# Sheet1.net
KiCad netlist of a schematic drawn in Altium Designer
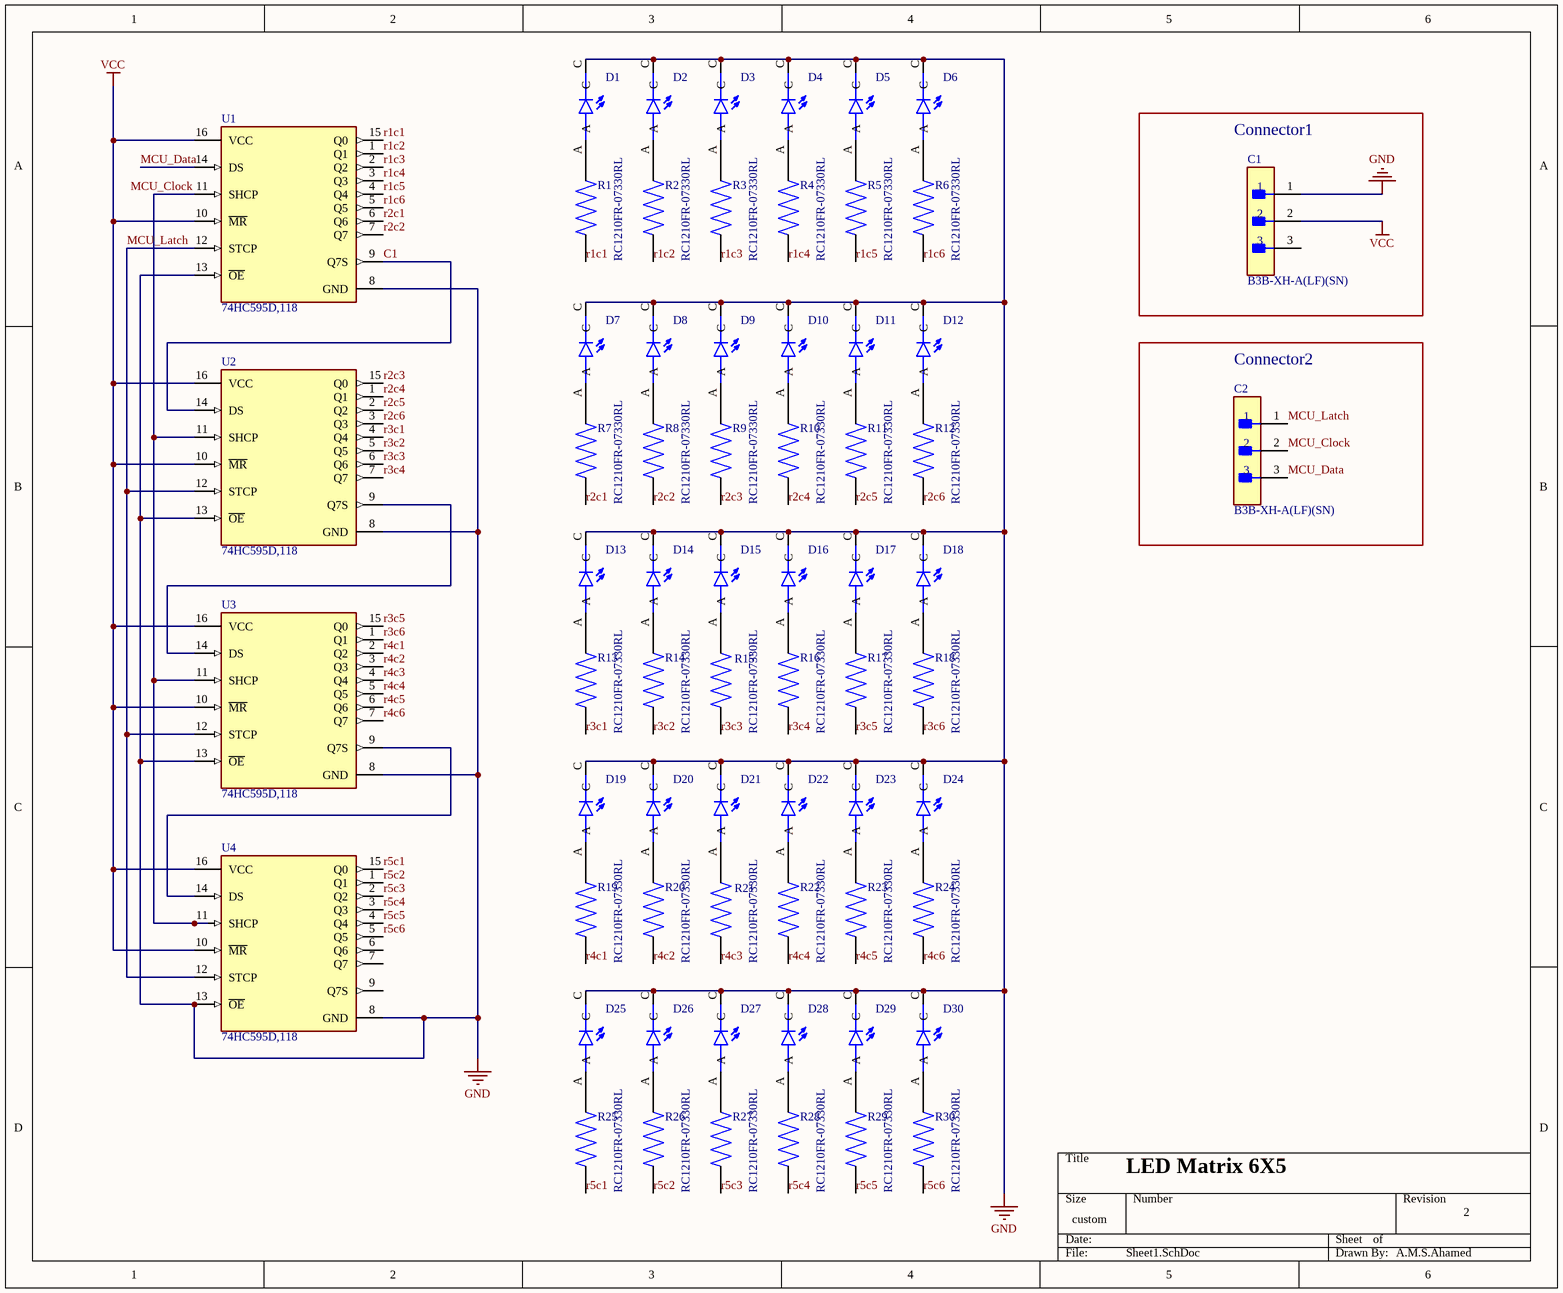
[diagram p0: Sheet1.SchDoc]

(export (version "E")
  (design (tool "Eeschema 10.0.6"))
  (components
    (comp (ref "C1")
      (value "B3B-XH-A(LF)(SN)")
      (footprint "FP-B3B-XH-A_LF_SN-MFG")
      (description "CONN HEADER VERT 3POS 2.5MM")
      (libsource (lib "Altium Content Vault") (part "0d3f023dd272f625e17a2be33dea85f"))
    )
    (comp (ref "C2")
      (value "B3B-XH-A(LF)(SN)")
      (footprint "FP-B3B-XH-A_LF_SN-MFG")
      (description "CONN HEADER VERT 3POS 2.5MM")
      (libsource (lib "Altium Content Vault") (part "0d3f023dd272f625e17a2be33dea85f"))
    )
    (comp (ref "D1")
      (value "WP7113ID")
      (footprint "LED_WP7113ID")
      (description "Red 617nm LED Indication - Discrete 2V Radial")
      (fields (field (name "MF") "Kingbright"))
      (libsource (lib "WP7113ID") (part "WP7113ID"))
    )
    (comp (ref "D2")
      (value "WP7113ID")
      (footprint "LED_WP7113ID")
      (description "Red 617nm LED Indication - Discrete 2V Radial")
      (fields (field (name "MF") "Kingbright"))
      (libsource (lib "WP7113ID") (part "WP7113ID"))
    )
    (comp (ref "D3")
      (value "WP7113ID")
      (footprint "LED_WP7113ID")
      (description "Red 617nm LED Indication - Discrete 2V Radial")
      (fields (field (name "MF") "Kingbright"))
      (libsource (lib "WP7113ID") (part "WP7113ID"))
    )
    (comp (ref "D4")
      (value "WP7113ID")
      (footprint "LED_WP7113ID")
      (description "Red 617nm LED Indication - Discrete 2V Radial")
      (fields (field (name "MF") "Kingbright"))
      (libsource (lib "WP7113ID") (part "WP7113ID"))
    )
    (comp (ref "D5")
      (value "WP7113ID")
      (footprint "LED_WP7113ID")
      (description "Red 617nm LED Indication - Discrete 2V Radial")
      (fields (field (name "MF") "Kingbright"))
      (libsource (lib "WP7113ID") (part "WP7113ID"))
    )
    (comp (ref "D6")
      (value "WP7113ID")
      (footprint "LED_WP7113ID")
      (description "Red 617nm LED Indication - Discrete 2V Radial")
      (fields (field (name "MF") "Kingbright"))
      (libsource (lib "WP7113ID") (part "WP7113ID"))
    )
    (comp (ref "D7")
      (value "WP7113ID")
      (footprint "LED_WP7113ID")
      (description "Red 617nm LED Indication - Discrete 2V Radial")
      (fields (field (name "MF") "Kingbright"))
      (libsource (lib "WP7113ID") (part "WP7113ID"))
    )
    (comp (ref "D8")
      (value "WP7113ID")
      (footprint "LED_WP7113ID")
      (description "Red 617nm LED Indication - Discrete 2V Radial")
      (fields (field (name "MF") "Kingbright"))
      (libsource (lib "WP7113ID") (part "WP7113ID"))
    )
    (comp (ref "D9")
      (value "WP7113ID")
      (footprint "LED_WP7113ID")
      (description "Red 617nm LED Indication - Discrete 2V Radial")
      (fields (field (name "MF") "Kingbright"))
      (libsource (lib "WP7113ID") (part "WP7113ID"))
    )
    (comp (ref "D10")
      (value "WP7113ID")
      (footprint "LED_WP7113ID")
      (description "Red 617nm LED Indication - Discrete 2V Radial")
      (fields (field (name "MF") "Kingbright"))
      (libsource (lib "WP7113ID") (part "WP7113ID"))
    )
    (comp (ref "D11")
      (value "WP7113ID")
      (footprint "LED_WP7113ID")
      (description "Red 617nm LED Indication - Discrete 2V Radial")
      (fields (field (name "MF") "Kingbright"))
      (libsource (lib "WP7113ID") (part "WP7113ID"))
    )
    (comp (ref "D12")
      (value "WP7113ID")
      (footprint "LED_WP7113ID")
      (description "Red 617nm LED Indication - Discrete 2V Radial")
      (fields (field (name "MF") "Kingbright"))
      (libsource (lib "WP7113ID") (part "WP7113ID"))
    )
    (comp (ref "D13")
      (value "WP7113ID")
      (footprint "LED_WP7113ID")
      (description "Red 617nm LED Indication - Discrete 2V Radial")
      (fields (field (name "MF") "Kingbright"))
      (libsource (lib "WP7113ID") (part "WP7113ID"))
    )
    (comp (ref "D14")
      (value "WP7113ID")
      (footprint "LED_WP7113ID")
      (description "Red 617nm LED Indication - Discrete 2V Radial")
      (fields (field (name "MF") "Kingbright"))
      (libsource (lib "WP7113ID") (part "WP7113ID"))
    )
    (comp (ref "D15")
      (value "WP7113ID")
      (footprint "LED_WP7113ID")
      (description "Red 617nm LED Indication - Discrete 2V Radial")
      (fields (field (name "MF") "Kingbright"))
      (libsource (lib "WP7113ID") (part "WP7113ID"))
    )
    (comp (ref "D16")
      (value "WP7113ID")
      (footprint "LED_WP7113ID")
      (description "Red 617nm LED Indication - Discrete 2V Radial")
      (fields (field (name "MF") "Kingbright"))
      (libsource (lib "WP7113ID") (part "WP7113ID"))
    )
    (comp (ref "D17")
      (value "WP7113ID")
      (footprint "LED_WP7113ID")
      (description "Red 617nm LED Indication - Discrete 2V Radial")
      (fields (field (name "MF") "Kingbright"))
      (libsource (lib "WP7113ID") (part "WP7113ID"))
    )
    (comp (ref "D18")
      (value "WP7113ID")
      (footprint "LED_WP7113ID")
      (description "Red 617nm LED Indication - Discrete 2V Radial")
      (fields (field (name "MF") "Kingbright"))
      (libsource (lib "WP7113ID") (part "WP7113ID"))
    )
    (comp (ref "D19")
      (value "WP7113ID")
      (footprint "LED_WP7113ID")
      (description "Red 617nm LED Indication - Discrete 2V Radial")
      (fields (field (name "MF") "Kingbright"))
      (libsource (lib "WP7113ID") (part "WP7113ID"))
    )
    (comp (ref "D20")
      (value "WP7113ID")
      (footprint "LED_WP7113ID")
      (description "Red 617nm LED Indication - Discrete 2V Radial")
      (fields (field (name "MF") "Kingbright"))
      (libsource (lib "WP7113ID") (part "WP7113ID"))
    )
    (comp (ref "D21")
      (value "WP7113ID")
      (footprint "LED_WP7113ID")
      (description "Red 617nm LED Indication - Discrete 2V Radial")
      (fields (field (name "MF") "Kingbright"))
      (libsource (lib "WP7113ID") (part "WP7113ID"))
    )
    (comp (ref "D22")
      (value "WP7113ID")
      (footprint "LED_WP7113ID")
      (description "Red 617nm LED Indication - Discrete 2V Radial")
      (fields (field (name "MF") "Kingbright"))
      (libsource (lib "WP7113ID") (part "WP7113ID"))
    )
    (comp (ref "D23")
      (value "WP7113ID")
      (footprint "LED_WP7113ID")
      (description "Red 617nm LED Indication - Discrete 2V Radial")
      (fields (field (name "MF") "Kingbright"))
      (libsource (lib "WP7113ID") (part "WP7113ID"))
    )
    (comp (ref "D24")
      (value "WP7113ID")
      (footprint "LED_WP7113ID")
      (description "Red 617nm LED Indication - Discrete 2V Radial")
      (fields (field (name "MF") "Kingbright"))
      (libsource (lib "WP7113ID") (part "WP7113ID"))
    )
    (comp (ref "D25")
      (value "WP7113ID")
      (footprint "LED_WP7113ID")
      (description "Red 617nm LED Indication - Discrete 2V Radial")
      (fields (field (name "MF") "Kingbright"))
      (libsource (lib "WP7113ID") (part "WP7113ID"))
    )
    (comp (ref "D26")
      (value "WP7113ID")
      (footprint "LED_WP7113ID")
      (description "Red 617nm LED Indication - Discrete 2V Radial")
      (fields (field (name "MF") "Kingbright"))
      (libsource (lib "WP7113ID") (part "WP7113ID"))
    )
    (comp (ref "D27")
      (value "WP7113ID")
      (footprint "LED_WP7113ID")
      (description "Red 617nm LED Indication - Discrete 2V Radial")
      (fields (field (name "MF") "Kingbright"))
      (libsource (lib "WP7113ID") (part "WP7113ID"))
    )
    (comp (ref "D28")
      (value "WP7113ID")
      (footprint "LED_WP7113ID")
      (description "Red 617nm LED Indication - Discrete 2V Radial")
      (fields (field (name "MF") "Kingbright"))
      (libsource (lib "WP7113ID") (part "WP7113ID"))
    )
    (comp (ref "D29")
      (value "WP7113ID")
      (footprint "LED_WP7113ID")
      (description "Red 617nm LED Indication - Discrete 2V Radial")
      (fields (field (name "MF") "Kingbright"))
      (libsource (lib "WP7113ID") (part "WP7113ID"))
    )
    (comp (ref "D30")
      (value "WP7113ID")
      (footprint "LED_WP7113ID")
      (description "Red 617nm LED Indication - Discrete 2V Radial")
      (fields (field (name "MF") "Kingbright"))
      (libsource (lib "WP7113ID") (part "WP7113ID"))
    )
    (comp (ref "R1")
      (value "RC1210FR-07330RL")
      (footprint "RESC3126X65N")
      (description "330 Ohms Â±1% 0.5W, 1/2W Chip Resistor 1210 (3225 Metric) Moisture Resistant Thick Film")
      (fields (field (name "MF") "Yageo"))
      (libsource (lib "RC1210FR-07330RL") (part "RC1210FR-07330RL"))
    )
    (comp (ref "R2")
      (value "RC1210FR-07330RL")
      (footprint "RESC3126X65N")
      (description "330 Ohms Â±1% 0.5W, 1/2W Chip Resistor 1210 (3225 Metric) Moisture Resistant Thick Film")
      (fields (field (name "MF") "Yageo"))
      (libsource (lib "RC1210FR-07330RL") (part "RC1210FR-07330RL"))
    )
    (comp (ref "R3")
      (value "RC1210FR-07330RL")
      (footprint "RESC3126X65N")
      (description "330 Ohms Â±1% 0.5W, 1/2W Chip Resistor 1210 (3225 Metric) Moisture Resistant Thick Film")
      (fields (field (name "MF") "Yageo"))
      (libsource (lib "RC1210FR-07330RL") (part "RC1210FR-07330RL"))
    )
    (comp (ref "R4")
      (value "RC1210FR-07330RL")
      (footprint "RESC3126X65N")
      (description "330 Ohms Â±1% 0.5W, 1/2W Chip Resistor 1210 (3225 Metric) Moisture Resistant Thick Film")
      (fields (field (name "MF") "Yageo"))
      (libsource (lib "RC1210FR-07330RL") (part "RC1210FR-07330RL"))
    )
    (comp (ref "R5")
      (value "RC1210FR-07330RL")
      (footprint "RESC3126X65N")
      (description "330 Ohms Â±1% 0.5W, 1/2W Chip Resistor 1210 (3225 Metric) Moisture Resistant Thick Film")
      (fields (field (name "MF") "Yageo"))
      (libsource (lib "RC1210FR-07330RL") (part "RC1210FR-07330RL"))
    )
    (comp (ref "R6")
      (value "RC1210FR-07330RL")
      (footprint "RESC3126X65N")
      (description "330 Ohms Â±1% 0.5W, 1/2W Chip Resistor 1210 (3225 Metric) Moisture Resistant Thick Film")
      (fields (field (name "MF") "Yageo"))
      (libsource (lib "RC1210FR-07330RL") (part "RC1210FR-07330RL"))
    )
    (comp (ref "R7")
      (value "RC1210FR-07330RL")
      (footprint "RESC3126X65N")
      (description "330 Ohms Â±1% 0.5W, 1/2W Chip Resistor 1210 (3225 Metric) Moisture Resistant Thick Film")
      (fields (field (name "MF") "Yageo"))
      (libsource (lib "RC1210FR-07330RL") (part "RC1210FR-07330RL"))
    )
    (comp (ref "R8")
      (value "RC1210FR-07330RL")
      (footprint "RESC3126X65N")
      (description "330 Ohms Â±1% 0.5W, 1/2W Chip Resistor 1210 (3225 Metric) Moisture Resistant Thick Film")
      (fields (field (name "MF") "Yageo"))
      (libsource (lib "RC1210FR-07330RL") (part "RC1210FR-07330RL"))
    )
    (comp (ref "R9")
      (value "RC1210FR-07330RL")
      (footprint "RESC3126X65N")
      (description "330 Ohms Â±1% 0.5W, 1/2W Chip Resistor 1210 (3225 Metric) Moisture Resistant Thick Film")
      (fields (field (name "MF") "Yageo"))
      (libsource (lib "RC1210FR-07330RL") (part "RC1210FR-07330RL"))
    )
    (comp (ref "R10")
      (value "RC1210FR-07330RL")
      (footprint "RESC3126X65N")
      (description "330 Ohms Â±1% 0.5W, 1/2W Chip Resistor 1210 (3225 Metric) Moisture Resistant Thick Film")
      (fields (field (name "MF") "Yageo"))
      (libsource (lib "RC1210FR-07330RL") (part "RC1210FR-07330RL"))
    )
    (comp (ref "R11")
      (value "RC1210FR-07330RL")
      (footprint "RESC3126X65N")
      (description "330 Ohms Â±1% 0.5W, 1/2W Chip Resistor 1210 (3225 Metric) Moisture Resistant Thick Film")
      (fields (field (name "MF") "Yageo"))
      (libsource (lib "RC1210FR-07330RL") (part "RC1210FR-07330RL"))
    )
    (comp (ref "R12")
      (value "RC1210FR-07330RL")
      (footprint "RESC3126X65N")
      (description "330 Ohms Â±1% 0.5W, 1/2W Chip Resistor 1210 (3225 Metric) Moisture Resistant Thick Film")
      (fields (field (name "MF") "Yageo"))
      (libsource (lib "RC1210FR-07330RL") (part "RC1210FR-07330RL"))
    )
    (comp (ref "R13")
      (value "RC1210FR-07330RL")
      (footprint "RESC3126X65N")
      (description "330 Ohms Â±1% 0.5W, 1/2W Chip Resistor 1210 (3225 Metric) Moisture Resistant Thick Film")
      (fields (field (name "MF") "Yageo"))
      (libsource (lib "RC1210FR-07330RL") (part "RC1210FR-07330RL"))
    )
    (comp (ref "R14")
      (value "RC1210FR-07330RL")
      (footprint "RESC3126X65N")
      (description "330 Ohms Â±1% 0.5W, 1/2W Chip Resistor 1210 (3225 Metric) Moisture Resistant Thick Film")
      (fields (field (name "MF") "Yageo"))
      (libsource (lib "RC1210FR-07330RL") (part "RC1210FR-07330RL"))
    )
    (comp (ref "R15")
      (value "RC1210FR-07330RL")
      (footprint "RESC3126X65N")
      (description "330 Ohms Â±1% 0.5W, 1/2W Chip Resistor 1210 (3225 Metric) Moisture Resistant Thick Film")
      (fields (field (name "MF") "Yageo"))
      (libsource (lib "RC1210FR-07330RL") (part "RC1210FR-07330RL"))
    )
    (comp (ref "R16")
      (value "RC1210FR-07330RL")
      (footprint "RESC3126X65N")
      (description "330 Ohms Â±1% 0.5W, 1/2W Chip Resistor 1210 (3225 Metric) Moisture Resistant Thick Film")
      (fields (field (name "MF") "Yageo"))
      (libsource (lib "RC1210FR-07330RL") (part "RC1210FR-07330RL"))
    )
    (comp (ref "R17")
      (value "RC1210FR-07330RL")
      (footprint "RESC3126X65N")
      (description "330 Ohms Â±1% 0.5W, 1/2W Chip Resistor 1210 (3225 Metric) Moisture Resistant Thick Film")
      (fields (field (name "MF") "Yageo"))
      (libsource (lib "RC1210FR-07330RL") (part "RC1210FR-07330RL"))
    )
    (comp (ref "R18")
      (value "RC1210FR-07330RL")
      (footprint "RESC3126X65N")
      (description "330 Ohms Â±1% 0.5W, 1/2W Chip Resistor 1210 (3225 Metric) Moisture Resistant Thick Film")
      (fields (field (name "MF") "Yageo"))
      (libsource (lib "RC1210FR-07330RL") (part "RC1210FR-07330RL"))
    )
    (comp (ref "R19")
      (value "RC1210FR-07330RL")
      (footprint "RESC3126X65N")
      (description "330 Ohms Â±1% 0.5W, 1/2W Chip Resistor 1210 (3225 Metric) Moisture Resistant Thick Film")
      (fields (field (name "MF") "Yageo"))
      (libsource (lib "RC1210FR-07330RL") (part "RC1210FR-07330RL"))
    )
    (comp (ref "R20")
      (value "RC1210FR-07330RL")
      (footprint "RESC3126X65N")
      (description "330 Ohms Â±1% 0.5W, 1/2W Chip Resistor 1210 (3225 Metric) Moisture Resistant Thick Film")
      (fields (field (name "MF") "Yageo"))
      (libsource (lib "RC1210FR-07330RL") (part "RC1210FR-07330RL"))
    )
    (comp (ref "R21")
      (value "RC1210FR-07330RL")
      (footprint "RESC3126X65N")
      (description "330 Ohms Â±1% 0.5W, 1/2W Chip Resistor 1210 (3225 Metric) Moisture Resistant Thick Film")
      (fields (field (name "MF") "Yageo"))
      (libsource (lib "RC1210FR-07330RL") (part "RC1210FR-07330RL"))
    )
    (comp (ref "R22")
      (value "RC1210FR-07330RL")
      (footprint "RESC3126X65N")
      (description "330 Ohms Â±1% 0.5W, 1/2W Chip Resistor 1210 (3225 Metric) Moisture Resistant Thick Film")
      (fields (field (name "MF") "Yageo"))
      (libsource (lib "RC1210FR-07330RL") (part "RC1210FR-07330RL"))
    )
    (comp (ref "R23")
      (value "RC1210FR-07330RL")
      (footprint "RESC3126X65N")
      (description "330 Ohms Â±1% 0.5W, 1/2W Chip Resistor 1210 (3225 Metric) Moisture Resistant Thick Film")
      (fields (field (name "MF") "Yageo"))
      (libsource (lib "RC1210FR-07330RL") (part "RC1210FR-07330RL"))
    )
    (comp (ref "R24")
      (value "RC1210FR-07330RL")
      (footprint "RESC3126X65N")
      (description "330 Ohms Â±1% 0.5W, 1/2W Chip Resistor 1210 (3225 Metric) Moisture Resistant Thick Film")
      (fields (field (name "MF") "Yageo"))
      (libsource (lib "RC1210FR-07330RL") (part "RC1210FR-07330RL"))
    )
    (comp (ref "R25")
      (value "RC1210FR-07330RL")
      (footprint "RESC3126X65N")
      (description "330 Ohms Â±1% 0.5W, 1/2W Chip Resistor 1210 (3225 Metric) Moisture Resistant Thick Film")
      (fields (field (name "MF") "Yageo"))
      (libsource (lib "RC1210FR-07330RL") (part "RC1210FR-07330RL"))
    )
    (comp (ref "R26")
      (value "RC1210FR-07330RL")
      (footprint "RESC3126X65N")
      (description "330 Ohms Â±1% 0.5W, 1/2W Chip Resistor 1210 (3225 Metric) Moisture Resistant Thick Film")
      (fields (field (name "MF") "Yageo"))
      (libsource (lib "RC1210FR-07330RL") (part "RC1210FR-07330RL"))
    )
    (comp (ref "R27")
      (value "RC1210FR-07330RL")
      (footprint "RESC3126X65N")
      (description "330 Ohms Â±1% 0.5W, 1/2W Chip Resistor 1210 (3225 Metric) Moisture Resistant Thick Film")
      (fields (field (name "MF") "Yageo"))
      (libsource (lib "RC1210FR-07330RL") (part "RC1210FR-07330RL"))
    )
    (comp (ref "R28")
      (value "RC1210FR-07330RL")
      (footprint "RESC3126X65N")
      (description "330 Ohms Â±1% 0.5W, 1/2W Chip Resistor 1210 (3225 Metric) Moisture Resistant Thick Film")
      (fields (field (name "MF") "Yageo"))
      (libsource (lib "RC1210FR-07330RL") (part "RC1210FR-07330RL"))
    )
    (comp (ref "R29")
      (value "RC1210FR-07330RL")
      (footprint "RESC3126X65N")
      (description "330 Ohms Â±1% 0.5W, 1/2W Chip Resistor 1210 (3225 Metric) Moisture Resistant Thick Film")
      (fields (field (name "MF") "Yageo"))
      (libsource (lib "RC1210FR-07330RL") (part "RC1210FR-07330RL"))
    )
    (comp (ref "R30")
      (value "RC1210FR-07330RL")
      (footprint "RESC3126X65N")
      (description "330 Ohms Â±1% 0.5W, 1/2W Chip Resistor 1210 (3225 Metric) Moisture Resistant Thick Film")
      (fields (field (name "MF") "Yageo"))
      (libsource (lib "RC1210FR-07330RL") (part "RC1210FR-07330RL"))
    )
    (comp (ref "U1")
      (value "74HC595D,118")
      (footprint "FP-SOT109-1-IPC_C")
      (description "IC SHIFT REGISTER 8BIT 16SOIC")
      (libsource (lib "Altium Content Vault") (part "7b153f231cfcc3ac06dee253bd56617"))
    )
    (comp (ref "U2")
      (value "74HC595D,118")
      (footprint "FP-SOT109-1-IPC_C")
      (description "IC SHIFT REGISTER 8BIT 16SOIC")
      (libsource (lib "Altium Content Vault") (part "7b153f231cfcc3ac06dee253bd56617"))
    )
    (comp (ref "U3")
      (value "74HC595D,118")
      (footprint "FP-SOT109-1-IPC_C")
      (description "IC SHIFT REGISTER 8BIT 16SOIC")
      (libsource (lib "Altium Content Vault") (part "7b153f231cfcc3ac06dee253bd56617"))
    )
    (comp (ref "U4")
      (value "74HC595D,118")
      (footprint "FP-SOT109-1-IPC_C")
      (description "IC SHIFT REGISTER 8BIT 16SOIC")
      (libsource (lib "Altium Content Vault") (part "7b153f231cfcc3ac06dee253bd56617"))
    )
  )
  (nets
    (net (code "1") (name "/C1") (class "Default")
      (node (ref "U1") (pin "9") (pinfunction "Q7S_9") (pintype "output"))
      (node (ref "U2") (pin "14") (pinfunction "DS_14") (pintype "input"))
    )
    (net (code "2") (name "/MCU_Clock") (class "Default")
      (node (ref "C2") (pin "2") (pinfunction "2_2") (pintype "passive"))
      (node (ref "U1") (pin "11") (pinfunction "SHCP_11") (pintype "input"))
      (node (ref "U2") (pin "11") (pinfunction "SHCP_11") (pintype "input"))
      (node (ref "U3") (pin "11") (pinfunction "SHCP_11") (pintype "input"))
      (node (ref "U4") (pin "11") (pinfunction "SHCP_11") (pintype "input"))
    )
    (net (code "3") (name "/MCU_Data") (class "Default")
      (node (ref "C2") (pin "3") (pinfunction "3_3") (pintype "passive"))
      (node (ref "U1") (pin "14") (pinfunction "DS_14") (pintype "input"))
    )
    (net (code "4") (name "/MCU_Latch") (class "Default")
      (node (ref "C2") (pin "1") (pinfunction "1_1") (pintype "passive"))
      (node (ref "U1") (pin "12") (pinfunction "STCP_12") (pintype "input"))
      (node (ref "U2") (pin "12") (pinfunction "STCP_12") (pintype "input"))
      (node (ref "U3") (pin "12") (pinfunction "STCP_12") (pintype "input"))
      (node (ref "U4") (pin "12") (pinfunction "STCP_12") (pintype "input"))
    )
    (net (code "5") (name "/r1c1") (class "Default")
      (node (ref "R1") (pin "1") (pinfunction "1_1") (pintype "passive"))
      (node (ref "U1") (pin "15") (pinfunction "Q0_15") (pintype "output"))
    )
    (net (code "6") (name "/r1c2") (class "Default")
      (node (ref "R2") (pin "1") (pinfunction "1_1") (pintype "passive"))
      (node (ref "U1") (pin "1") (pinfunction "Q1_1") (pintype "output"))
    )
    (net (code "7") (name "/r1c3") (class "Default")
      (node (ref "R3") (pin "1") (pinfunction "1_1") (pintype "passive"))
      (node (ref "U1") (pin "2") (pinfunction "Q2_2") (pintype "output"))
    )
    (net (code "8") (name "/r1c4") (class "Default")
      (node (ref "R4") (pin "1") (pinfunction "1_1") (pintype "passive"))
      (node (ref "U1") (pin "3") (pinfunction "Q3_3") (pintype "output"))
    )
    (net (code "9") (name "/r1c5") (class "Default")
      (node (ref "R5") (pin "1") (pinfunction "1_1") (pintype "passive"))
      (node (ref "U1") (pin "4") (pinfunction "Q4_4") (pintype "output"))
    )
    (net (code "10") (name "/r1c6") (class "Default")
      (node (ref "R6") (pin "1") (pinfunction "1_1") (pintype "passive"))
      (node (ref "U1") (pin "5") (pinfunction "Q5_5") (pintype "output"))
    )
    (net (code "11") (name "/r2c1") (class "Default")
      (node (ref "R7") (pin "1") (pinfunction "1_1") (pintype "passive"))
      (node (ref "U1") (pin "6") (pinfunction "Q6_6") (pintype "output"))
    )
    (net (code "12") (name "/r2c2") (class "Default")
      (node (ref "R8") (pin "1") (pinfunction "1_1") (pintype "passive"))
      (node (ref "U1") (pin "7") (pinfunction "Q7_7") (pintype "output"))
    )
    (net (code "13") (name "/r2c3") (class "Default")
      (node (ref "R9") (pin "1") (pinfunction "1_1") (pintype "passive"))
      (node (ref "U2") (pin "15") (pinfunction "Q0_15") (pintype "output"))
    )
    (net (code "14") (name "/r2c4") (class "Default")
      (node (ref "R10") (pin "1") (pinfunction "1_1") (pintype "passive"))
      (node (ref "U2") (pin "1") (pinfunction "Q1_1") (pintype "output"))
    )
    (net (code "15") (name "/r2c5") (class "Default")
      (node (ref "R11") (pin "1") (pinfunction "1_1") (pintype "passive"))
      (node (ref "U2") (pin "2") (pinfunction "Q2_2") (pintype "output"))
    )
    (net (code "16") (name "/r2c6") (class "Default")
      (node (ref "R12") (pin "1") (pinfunction "1_1") (pintype "passive"))
      (node (ref "U2") (pin "3") (pinfunction "Q3_3") (pintype "output"))
    )
    (net (code "17") (name "/r3c1") (class "Default")
      (node (ref "R13") (pin "1") (pinfunction "1_1") (pintype "passive"))
      (node (ref "U2") (pin "4") (pinfunction "Q4_4") (pintype "output"))
    )
    (net (code "18") (name "/r3c2") (class "Default")
      (node (ref "R14") (pin "1") (pinfunction "1_1") (pintype "passive"))
      (node (ref "U2") (pin "5") (pinfunction "Q5_5") (pintype "output"))
    )
    (net (code "19") (name "/r3c3") (class "Default")
      (node (ref "R15") (pin "1") (pinfunction "1_1") (pintype "passive"))
      (node (ref "U2") (pin "6") (pinfunction "Q6_6") (pintype "output"))
    )
    (net (code "20") (name "/r3c4") (class "Default")
      (node (ref "R16") (pin "1") (pinfunction "1_1") (pintype "passive"))
      (node (ref "U2") (pin "7") (pinfunction "Q7_7") (pintype "output"))
    )
    (net (code "21") (name "/r3c5") (class "Default")
      (node (ref "R17") (pin "1") (pinfunction "1_1") (pintype "passive"))
      (node (ref "U3") (pin "15") (pinfunction "Q0_15") (pintype "output"))
    )
    (net (code "22") (name "/r3c6") (class "Default")
      (node (ref "R18") (pin "1") (pinfunction "1_1") (pintype "passive"))
      (node (ref "U3") (pin "1") (pinfunction "Q1_1") (pintype "output"))
    )
    (net (code "23") (name "/r4c1") (class "Default")
      (node (ref "R19") (pin "1") (pinfunction "1_1") (pintype "passive"))
      (node (ref "U3") (pin "2") (pinfunction "Q2_2") (pintype "output"))
    )
    (net (code "24") (name "/r4c2") (class "Default")
      (node (ref "R20") (pin "1") (pinfunction "1_1") (pintype "passive"))
      (node (ref "U3") (pin "3") (pinfunction "Q3_3") (pintype "output"))
    )
    (net (code "25") (name "/r4c3") (class "Default")
      (node (ref "R21") (pin "1") (pinfunction "1_1") (pintype "passive"))
      (node (ref "U3") (pin "4") (pinfunction "Q4_4") (pintype "output"))
    )
    (net (code "26") (name "/r4c4") (class "Default")
      (node (ref "R22") (pin "1") (pinfunction "1_1") (pintype "passive"))
      (node (ref "U3") (pin "5") (pinfunction "Q5_5") (pintype "output"))
    )
    (net (code "27") (name "/r4c5") (class "Default")
      (node (ref "R23") (pin "1") (pinfunction "1_1") (pintype "passive"))
      (node (ref "U3") (pin "6") (pinfunction "Q6_6") (pintype "output"))
    )
    (net (code "28") (name "/r4c6") (class "Default")
      (node (ref "R24") (pin "1") (pinfunction "1_1") (pintype "passive"))
      (node (ref "U3") (pin "7") (pinfunction "Q7_7") (pintype "output"))
    )
    (net (code "29") (name "/r5c1") (class "Default")
      (node (ref "R25") (pin "1") (pinfunction "1_1") (pintype "passive"))
      (node (ref "U4") (pin "15") (pinfunction "Q0_15") (pintype "output"))
    )
    (net (code "30") (name "/r5c2") (class "Default")
      (node (ref "R26") (pin "1") (pinfunction "1_1") (pintype "passive"))
      (node (ref "U4") (pin "1") (pinfunction "Q1_1") (pintype "output"))
    )
    (net (code "31") (name "/r5c3") (class "Default")
      (node (ref "R27") (pin "1") (pinfunction "1_1") (pintype "passive"))
      (node (ref "U4") (pin "2") (pinfunction "Q2_2") (pintype "output"))
    )
    (net (code "32") (name "/r5c4") (class "Default")
      (node (ref "R28") (pin "1") (pinfunction "1_1") (pintype "passive"))
      (node (ref "U4") (pin "3") (pinfunction "Q3_3") (pintype "output"))
    )
    (net (code "33") (name "/r5c5") (class "Default")
      (node (ref "R29") (pin "1") (pinfunction "1_1") (pintype "passive"))
      (node (ref "U4") (pin "4") (pinfunction "Q4_4") (pintype "output"))
    )
    (net (code "34") (name "/r5c6") (class "Default")
      (node (ref "R30") (pin "1") (pinfunction "1_1") (pintype "passive"))
      (node (ref "U4") (pin "5") (pinfunction "Q5_5") (pintype "output"))
    )
    (net (code "35") (name "GND") (class "Default")
      (node (ref "C1") (pin "1") (pinfunction "1_1") (pintype "passive"))
      (node (ref "D1") (pin "C") (pinfunction "C_C") (pintype "passive"))
      (node (ref "D10") (pin "C") (pinfunction "C_C") (pintype "passive"))
      (node (ref "D11") (pin "C") (pinfunction "C_C") (pintype "passive"))
      (node (ref "D12") (pin "C") (pinfunction "C_C") (pintype "passive"))
      (node (ref "D13") (pin "C") (pinfunction "C_C") (pintype "passive"))
      (node (ref "D14") (pin "C") (pinfunction "C_C") (pintype "passive"))
      (node (ref "D15") (pin "C") (pinfunction "C_C") (pintype "passive"))
      (node (ref "D16") (pin "C") (pinfunction "C_C") (pintype "passive"))
      (node (ref "D17") (pin "C") (pinfunction "C_C") (pintype "passive"))
      (node (ref "D18") (pin "C") (pinfunction "C_C") (pintype "passive"))
      (node (ref "D19") (pin "C") (pinfunction "C_C") (pintype "passive"))
      (node (ref "D2") (pin "C") (pinfunction "C_C") (pintype "passive"))
      (node (ref "D20") (pin "C") (pinfunction "C_C") (pintype "passive"))
      (node (ref "D21") (pin "C") (pinfunction "C_C") (pintype "passive"))
      (node (ref "D22") (pin "C") (pinfunction "C_C") (pintype "passive"))
      (node (ref "D23") (pin "C") (pinfunction "C_C") (pintype "passive"))
      (node (ref "D24") (pin "C") (pinfunction "C_C") (pintype "passive"))
      (node (ref "D25") (pin "C") (pinfunction "C_C") (pintype "passive"))
      (node (ref "D26") (pin "C") (pinfunction "C_C") (pintype "passive"))
      (node (ref "D27") (pin "C") (pinfunction "C_C") (pintype "passive"))
      (node (ref "D28") (pin "C") (pinfunction "C_C") (pintype "passive"))
      (node (ref "D29") (pin "C") (pinfunction "C_C") (pintype "passive"))
      (node (ref "D3") (pin "C") (pinfunction "C_C") (pintype "passive"))
      (node (ref "D30") (pin "C") (pinfunction "C_C") (pintype "passive"))
      (node (ref "D4") (pin "C") (pinfunction "C_C") (pintype "passive"))
      (node (ref "D5") (pin "C") (pinfunction "C_C") (pintype "passive"))
      (node (ref "D6") (pin "C") (pinfunction "C_C") (pintype "passive"))
      (node (ref "D7") (pin "C") (pinfunction "C_C") (pintype "passive"))
      (node (ref "D8") (pin "C") (pinfunction "C_C") (pintype "passive"))
      (node (ref "D9") (pin "C") (pinfunction "C_C") (pintype "passive"))
      (node (ref "U1") (pin "13") (pinfunction "~{OE}_13") (pintype "input"))
      (node (ref "U1") (pin "8") (pinfunction "GND_8") (pintype "power_in"))
      (node (ref "U2") (pin "13") (pinfunction "~{OE}_13") (pintype "input"))
      (node (ref "U2") (pin "8") (pinfunction "GND_8") (pintype "power_in"))
      (node (ref "U3") (pin "13") (pinfunction "~{OE}_13") (pintype "input"))
      (node (ref "U3") (pin "8") (pinfunction "GND_8") (pintype "power_in"))
      (node (ref "U4") (pin "13") (pinfunction "~{OE}_13") (pintype "input"))
      (node (ref "U4") (pin "8") (pinfunction "GND_8") (pintype "power_in"))
    )
    (net (code "36") (name "Net-(D1-PadA)") (class "Default")
      (node (ref "D1") (pin "A") (pinfunction "A_A") (pintype "passive"))
      (node (ref "R1") (pin "2") (pinfunction "2_2") (pintype "passive"))
    )
    (net (code "37") (name "Net-(D2-PadA)") (class "Default")
      (node (ref "D2") (pin "A") (pinfunction "A_A") (pintype "passive"))
      (node (ref "R2") (pin "2") (pinfunction "2_2") (pintype "passive"))
    )
    (net (code "38") (name "Net-(D3-PadA)") (class "Default")
      (node (ref "D3") (pin "A") (pinfunction "A_A") (pintype "passive"))
      (node (ref "R3") (pin "2") (pinfunction "2_2") (pintype "passive"))
    )
    (net (code "39") (name "Net-(D4-PadA)") (class "Default")
      (node (ref "D4") (pin "A") (pinfunction "A_A") (pintype "passive"))
      (node (ref "R4") (pin "2") (pinfunction "2_2") (pintype "passive"))
    )
    (net (code "40") (name "Net-(D5-PadA)") (class "Default")
      (node (ref "D5") (pin "A") (pinfunction "A_A") (pintype "passive"))
      (node (ref "R5") (pin "2") (pinfunction "2_2") (pintype "passive"))
    )
    (net (code "41") (name "Net-(D6-PadA)") (class "Default")
      (node (ref "D6") (pin "A") (pinfunction "A_A") (pintype "passive"))
      (node (ref "R6") (pin "2") (pinfunction "2_2") (pintype "passive"))
    )
    (net (code "42") (name "Net-(D7-PadA)") (class "Default")
      (node (ref "D7") (pin "A") (pinfunction "A_A") (pintype "passive"))
      (node (ref "R7") (pin "2") (pinfunction "2_2") (pintype "passive"))
    )
    (net (code "43") (name "Net-(D8-PadA)") (class "Default")
      (node (ref "D8") (pin "A") (pinfunction "A_A") (pintype "passive"))
      (node (ref "R8") (pin "2") (pinfunction "2_2") (pintype "passive"))
    )
    (net (code "44") (name "Net-(D9-PadA)") (class "Default")
      (node (ref "D9") (pin "A") (pinfunction "A_A") (pintype "passive"))
      (node (ref "R9") (pin "2") (pinfunction "2_2") (pintype "passive"))
    )
    (net (code "45") (name "Net-(D10-PadA)") (class "Default")
      (node (ref "D10") (pin "A") (pinfunction "A_A") (pintype "passive"))
      (node (ref "R10") (pin "2") (pinfunction "2_2") (pintype "passive"))
    )
    (net (code "46") (name "Net-(D11-PadA)") (class "Default")
      (node (ref "D11") (pin "A") (pinfunction "A_A") (pintype "passive"))
      (node (ref "R11") (pin "2") (pinfunction "2_2") (pintype "passive"))
    )
    (net (code "47") (name "Net-(D12-PadA)") (class "Default")
      (node (ref "D12") (pin "A") (pinfunction "A_A") (pintype "passive"))
      (node (ref "R12") (pin "2") (pinfunction "2_2") (pintype "passive"))
    )
    (net (code "48") (name "Net-(D13-PadA)") (class "Default")
      (node (ref "D13") (pin "A") (pinfunction "A_A") (pintype "passive"))
      (node (ref "R13") (pin "2") (pinfunction "2_2") (pintype "passive"))
    )
    (net (code "49") (name "Net-(D14-PadA)") (class "Default")
      (node (ref "D14") (pin "A") (pinfunction "A_A") (pintype "passive"))
      (node (ref "R14") (pin "2") (pinfunction "2_2") (pintype "passive"))
    )
    (net (code "50") (name "Net-(D15-PadA)") (class "Default")
      (node (ref "D15") (pin "A") (pinfunction "A_A") (pintype "passive"))
      (node (ref "R15") (pin "2") (pinfunction "2_2") (pintype "passive"))
    )
    (net (code "51") (name "Net-(D16-PadA)") (class "Default")
      (node (ref "D16") (pin "A") (pinfunction "A_A") (pintype "passive"))
      (node (ref "R16") (pin "2") (pinfunction "2_2") (pintype "passive"))
    )
    (net (code "52") (name "Net-(D17-PadA)") (class "Default")
      (node (ref "D17") (pin "A") (pinfunction "A_A") (pintype "passive"))
      (node (ref "R17") (pin "2") (pinfunction "2_2") (pintype "passive"))
    )
    (net (code "53") (name "Net-(D18-PadA)") (class "Default")
      (node (ref "D18") (pin "A") (pinfunction "A_A") (pintype "passive"))
      (node (ref "R18") (pin "2") (pinfunction "2_2") (pintype "passive"))
    )
    (net (code "54") (name "Net-(D19-PadA)") (class "Default")
      (node (ref "D19") (pin "A") (pinfunction "A_A") (pintype "passive"))
      (node (ref "R19") (pin "2") (pinfunction "2_2") (pintype "passive"))
    )
    (net (code "55") (name "Net-(D20-PadA)") (class "Default")
      (node (ref "D20") (pin "A") (pinfunction "A_A") (pintype "passive"))
      (node (ref "R20") (pin "2") (pinfunction "2_2") (pintype "passive"))
    )
    (net (code "56") (name "Net-(D21-PadA)") (class "Default")
      (node (ref "D21") (pin "A") (pinfunction "A_A") (pintype "passive"))
      (node (ref "R21") (pin "2") (pinfunction "2_2") (pintype "passive"))
    )
    (net (code "57") (name "Net-(D22-PadA)") (class "Default")
      (node (ref "D22") (pin "A") (pinfunction "A_A") (pintype "passive"))
      (node (ref "R22") (pin "2") (pinfunction "2_2") (pintype "passive"))
    )
    (net (code "58") (name "Net-(D23-PadA)") (class "Default")
      (node (ref "D23") (pin "A") (pinfunction "A_A") (pintype "passive"))
      (node (ref "R23") (pin "2") (pinfunction "2_2") (pintype "passive"))
    )
    (net (code "59") (name "Net-(D24-PadA)") (class "Default")
      (node (ref "D24") (pin "A") (pinfunction "A_A") (pintype "passive"))
      (node (ref "R24") (pin "2") (pinfunction "2_2") (pintype "passive"))
    )
    (net (code "60") (name "Net-(D25-PadA)") (class "Default")
      (node (ref "D25") (pin "A") (pinfunction "A_A") (pintype "passive"))
      (node (ref "R25") (pin "2") (pinfunction "2_2") (pintype "passive"))
    )
    (net (code "61") (name "Net-(D26-PadA)") (class "Default")
      (node (ref "D26") (pin "A") (pinfunction "A_A") (pintype "passive"))
      (node (ref "R26") (pin "2") (pinfunction "2_2") (pintype "passive"))
    )
    (net (code "62") (name "Net-(D27-PadA)") (class "Default")
      (node (ref "D27") (pin "A") (pinfunction "A_A") (pintype "passive"))
      (node (ref "R27") (pin "2") (pinfunction "2_2") (pintype "passive"))
    )
    (net (code "63") (name "Net-(D28-PadA)") (class "Default")
      (node (ref "D28") (pin "A") (pinfunction "A_A") (pintype "passive"))
      (node (ref "R28") (pin "2") (pinfunction "2_2") (pintype "passive"))
    )
    (net (code "64") (name "Net-(D29-PadA)") (class "Default")
      (node (ref "D29") (pin "A") (pinfunction "A_A") (pintype "passive"))
      (node (ref "R29") (pin "2") (pinfunction "2_2") (pintype "passive"))
    )
    (net (code "65") (name "Net-(D30-PadA)") (class "Default")
      (node (ref "D30") (pin "A") (pinfunction "A_A") (pintype "passive"))
      (node (ref "R30") (pin "2") (pinfunction "2_2") (pintype "passive"))
    )
    (net (code "66") (name "Net-(U2-Q7S)") (class "Default")
      (node (ref "U2") (pin "9") (pinfunction "Q7S_9") (pintype "output"))
      (node (ref "U3") (pin "14") (pinfunction "DS_14") (pintype "input"))
    )
    (net (code "67") (name "Net-(U3-Q7S)") (class "Default")
      (node (ref "U3") (pin "9") (pinfunction "Q7S_9") (pintype "output"))
      (node (ref "U4") (pin "14") (pinfunction "DS_14") (pintype "input"))
    )
    (net (code "68") (name "VCC") (class "Default")
      (node (ref "C1") (pin "2") (pinfunction "2_2") (pintype "passive"))
      (node (ref "U1") (pin "10") (pinfunction "~{MR}_10") (pintype "input"))
      (node (ref "U1") (pin "16") (pinfunction "VCC_16") (pintype "power_in"))
      (node (ref "U2") (pin "10") (pinfunction "~{MR}_10") (pintype "input"))
      (node (ref "U2") (pin "16") (pinfunction "VCC_16") (pintype "power_in"))
      (node (ref "U3") (pin "10") (pinfunction "~{MR}_10") (pintype "input"))
      (node (ref "U3") (pin "16") (pinfunction "VCC_16") (pintype "power_in"))
      (node (ref "U4") (pin "10") (pinfunction "~{MR}_10") (pintype "input"))
      (node (ref "U4") (pin "16") (pinfunction "VCC_16") (pintype "power_in"))
    )
    (net (code "69") (name "unconnected-(C1-Pad3)") (class "Default")
      (node (ref "C1") (pin "3") (pinfunction "3_3") (pintype "passive"))
    )
    (net (code "70") (name "unconnected-(U4-Q6-Pad6)") (class "Default")
      (node (ref "U4") (pin "6") (pinfunction "Q6_6") (pintype "output"))
    )
    (net (code "71") (name "unconnected-(U4-Q7-Pad7)") (class "Default")
      (node (ref "U4") (pin "7") (pinfunction "Q7_7") (pintype "output"))
    )
    (net (code "72") (name "unconnected-(U4-Q7S-Pad9)") (class "Default")
      (node (ref "U4") (pin "9") (pinfunction "Q7S_9") (pintype "output"))
    )
  )
)
